# SCH_rp2040ArtDriver_2022-06-08.net
KiCad netlist of a schematic drawn in EasyEDA
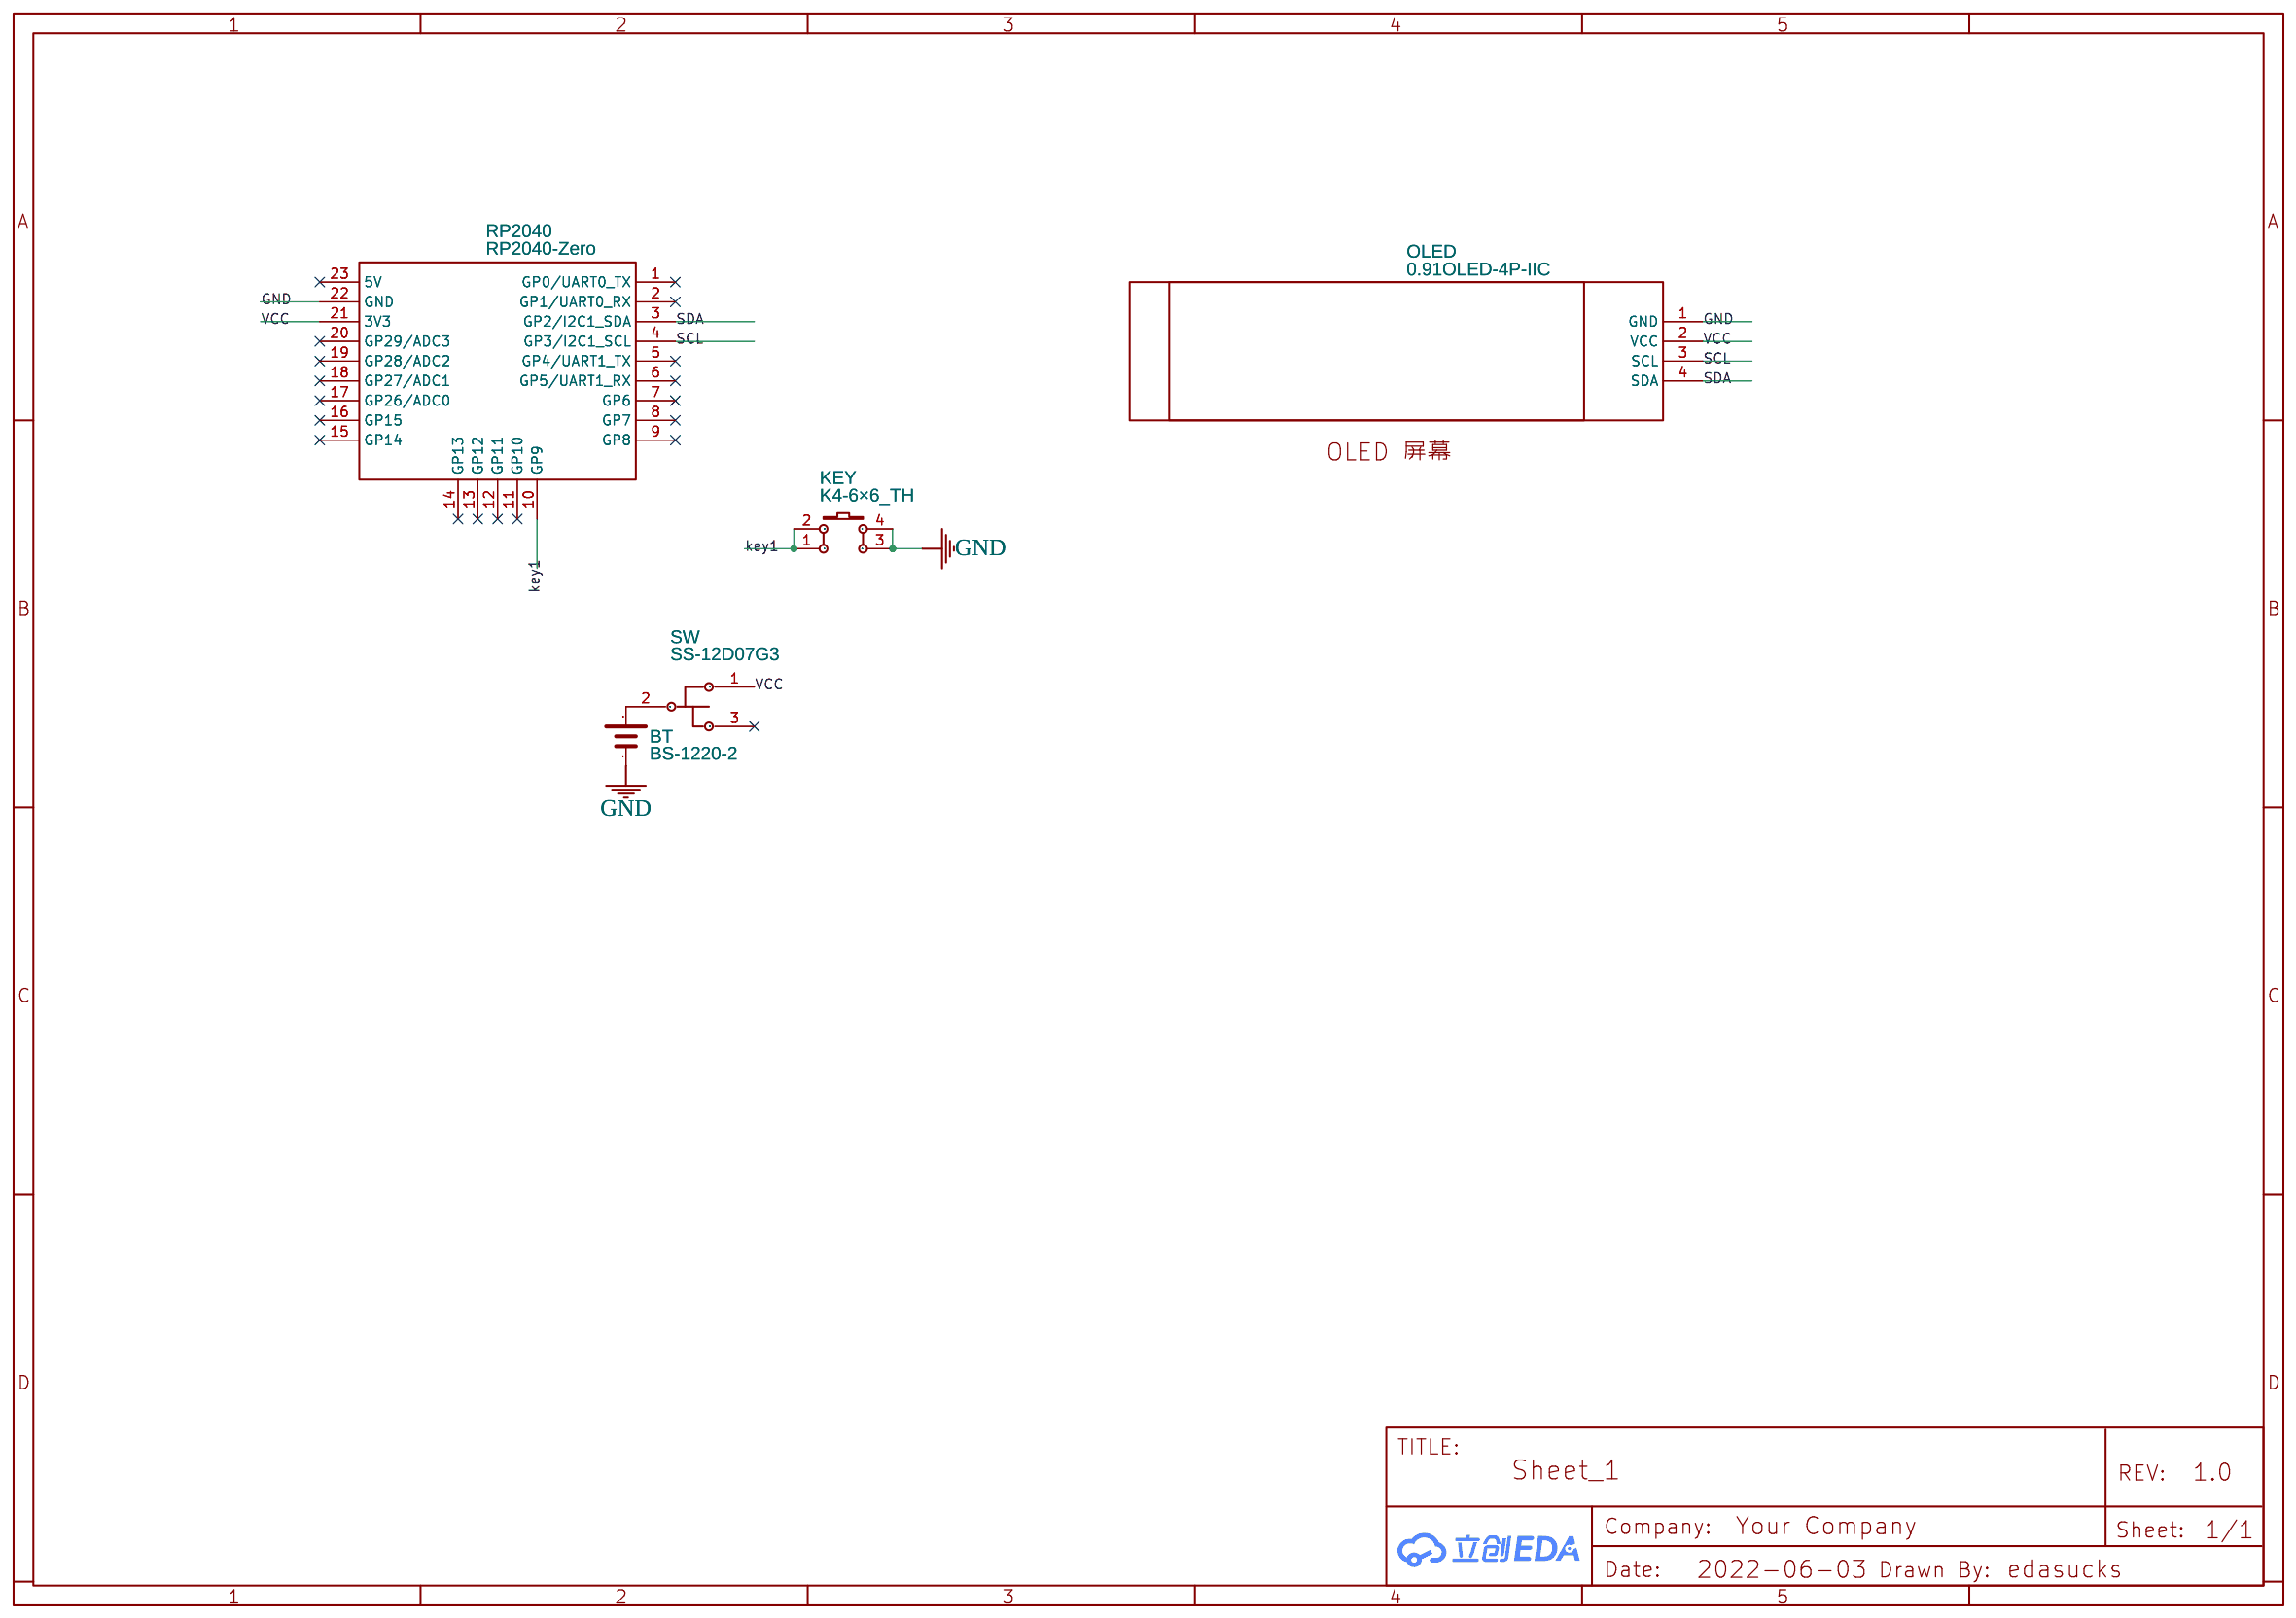
[diagram p0: schematic sheet]

(export (version "E")
  (design (tool "Eeschema 10.0.6"))
  (components
    (comp (ref "BT") (value "BS-1220-2") (libsource (lib "") (part "BS-1220-2")))
    (comp (ref "KEY")
      (value "K4-6×6_TH")
      (fields
        (field (name "BOM_Manufacturer Part") "K2-1102DP-E4SW-04")
        (field (name "BOM_Supplier Part") "C136684")
      )
      (libsource (lib "") (part "K4-6×6_TH"))
    )
    (comp (ref "OLED") (value "0.91OLED-4P-IIC") (libsource (lib "") (part "0.91OLED-4P-IIC")))
    (comp (ref "RP2040") (value "RP2040-Zero") (libsource (lib "") (part "RP2040-Zero")))
    (comp (ref "SW")
      (value "SS-12D07G3")
      (fields (field (name "BOM_Supplier Part") "C64633"))
      (libsource (lib "") (part "SS-12D07G3"))
    )
  )
  (nets
    (net (code "1") (name "/SCL") (class "Default")
      (node (ref "OLED") (pin "3") (pinfunction "SCL_3") (pintype "unspecified"))
      (node (ref "RP2040") (pin "4") (pinfunction "GP3/I2C1_SCL_4") (pintype "unspecified"))
    )
    (net (code "2") (name "/SDA") (class "Default")
      (node (ref "OLED") (pin "4") (pinfunction "SDA_4") (pintype "unspecified"))
      (node (ref "RP2040") (pin "3") (pinfunction "GP2/I2C1_SDA_3") (pintype "unspecified"))
    )
    (net (code "3") (name "/VCC") (class "Default")
      (node (ref "OLED") (pin "2") (pinfunction "VCC_2") (pintype "unspecified"))
      (node (ref "RP2040") (pin "21") (pinfunction "3V3_21") (pintype "unspecified"))
      (node (ref "SW") (pin "1") (pinfunction "1_1") (pintype "unspecified"))
    )
    (net (code "4") (name "/key1") (class "Default")
      (node (ref "KEY") (pin "1") (pinfunction "1_1") (pintype "unspecified"))
      (node (ref "KEY") (pin "2") (pinfunction "2_2") (pintype "unspecified"))
      (node (ref "RP2040") (pin "10") (pinfunction "GP9_10") (pintype "unspecified"))
    )
    (net (code "5") (name "GND") (class "Default")
      (node (ref "BT") (pin "2") (pintype "unspecified"))
      (node (ref "KEY") (pin "3") (pinfunction "3_3") (pintype "unspecified"))
      (node (ref "KEY") (pin "4") (pinfunction "4_4") (pintype "unspecified"))
      (node (ref "OLED") (pin "1") (pinfunction "GND_1") (pintype "unspecified"))
      (node (ref "RP2040") (pin "22") (pinfunction "GND_22") (pintype "unspecified"))
    )
    (net (code "6") (name "Net-(BT-Pad1)") (class "Default")
      (node (ref "BT") (pin "1") (pintype "unspecified"))
      (node (ref "SW") (pin "2") (pinfunction "2_2") (pintype "unspecified"))
    )
    (net (code "7") (name "unconnected-(RP2040-5V-Pad23)") (class "Default")
      (node (ref "RP2040") (pin "23") (pinfunction "5V_23") (pintype "unspecified+no_connect"))
    )
    (net (code "8") (name "unconnected-(RP2040-GP0{slash}UART0_TX-Pad1)") (class "Default")
      (node (ref "RP2040") (pin "1") (pinfunction "GP0/UART0_TX_1") (pintype "unspecified+no_connect"))
    )
    (net (code "9") (name "unconnected-(RP2040-GP1{slash}UART0_RX-Pad2)") (class "Default")
      (node (ref "RP2040") (pin "2") (pinfunction "GP1/UART0_RX_2") (pintype "unspecified+no_connect"))
    )
    (net (code "10") (name "unconnected-(RP2040-GP4{slash}UART1_TX-Pad5)") (class "Default")
      (node (ref "RP2040") (pin "5") (pinfunction "GP4/UART1_TX_5") (pintype "unspecified+no_connect"))
    )
    (net (code "11") (name "unconnected-(RP2040-GP5{slash}UART1_RX-Pad6)") (class "Default")
      (node (ref "RP2040") (pin "6") (pinfunction "GP5/UART1_RX_6") (pintype "unspecified+no_connect"))
    )
    (net (code "12") (name "unconnected-(RP2040-GP6-Pad7)") (class "Default")
      (node (ref "RP2040") (pin "7") (pinfunction "GP6_7") (pintype "unspecified+no_connect"))
    )
    (net (code "13") (name "unconnected-(RP2040-GP7-Pad8)") (class "Default")
      (node (ref "RP2040") (pin "8") (pinfunction "GP7_8") (pintype "unspecified+no_connect"))
    )
    (net (code "14") (name "unconnected-(RP2040-GP8-Pad9)") (class "Default")
      (node (ref "RP2040") (pin "9") (pinfunction "GP8_9") (pintype "unspecified+no_connect"))
    )
    (net (code "15") (name "unconnected-(RP2040-GP10-Pad11)") (class "Default")
      (node (ref "RP2040") (pin "11") (pinfunction "GP10_11") (pintype "unspecified+no_connect"))
    )
    (net (code "16") (name "unconnected-(RP2040-GP11-Pad12)") (class "Default")
      (node (ref "RP2040") (pin "12") (pinfunction "GP11_12") (pintype "unspecified+no_connect"))
    )
    (net (code "17") (name "unconnected-(RP2040-GP12-Pad13)") (class "Default")
      (node (ref "RP2040") (pin "13") (pinfunction "GP12_13") (pintype "unspecified+no_connect"))
    )
    (net (code "18") (name "unconnected-(RP2040-GP13-Pad14)") (class "Default")
      (node (ref "RP2040") (pin "14") (pinfunction "GP13_14") (pintype "unspecified+no_connect"))
    )
    (net (code "19") (name "unconnected-(RP2040-GP14-Pad15)") (class "Default")
      (node (ref "RP2040") (pin "15") (pinfunction "GP14_15") (pintype "unspecified+no_connect"))
    )
    (net (code "20") (name "unconnected-(RP2040-GP15-Pad16)") (class "Default")
      (node (ref "RP2040") (pin "16") (pinfunction "GP15_16") (pintype "unspecified+no_connect"))
    )
    (net (code "21") (name "unconnected-(RP2040-GP26{slash}ADC0-Pad17)") (class "Default")
      (node (ref "RP2040") (pin "17") (pinfunction "GP26/ADC0_17") (pintype "unspecified+no_connect"))
    )
    (net (code "22") (name "unconnected-(RP2040-GP27{slash}ADC1-Pad18)") (class "Default")
      (node (ref "RP2040") (pin "18") (pinfunction "GP27/ADC1_18") (pintype "unspecified+no_connect"))
    )
    (net (code "23") (name "unconnected-(RP2040-GP28{slash}ADC2-Pad19)") (class "Default")
      (node (ref "RP2040") (pin "19") (pinfunction "GP28/ADC2_19") (pintype "unspecified+no_connect"))
    )
    (net (code "24") (name "unconnected-(RP2040-GP29{slash}ADC3-Pad20)") (class "Default")
      (node (ref "RP2040") (pin "20") (pinfunction "GP29/ADC3_20") (pintype "unspecified+no_connect"))
    )
    (net (code "25") (name "unconnected-(SW-Pad3)") (class "Default")
      (node (ref "SW") (pin "3") (pinfunction "3_3") (pintype "unspecified+no_connect"))
    )
  )
)
